# HG-Badge6.net
KiCad netlist of a schematic drawn in EAGLE
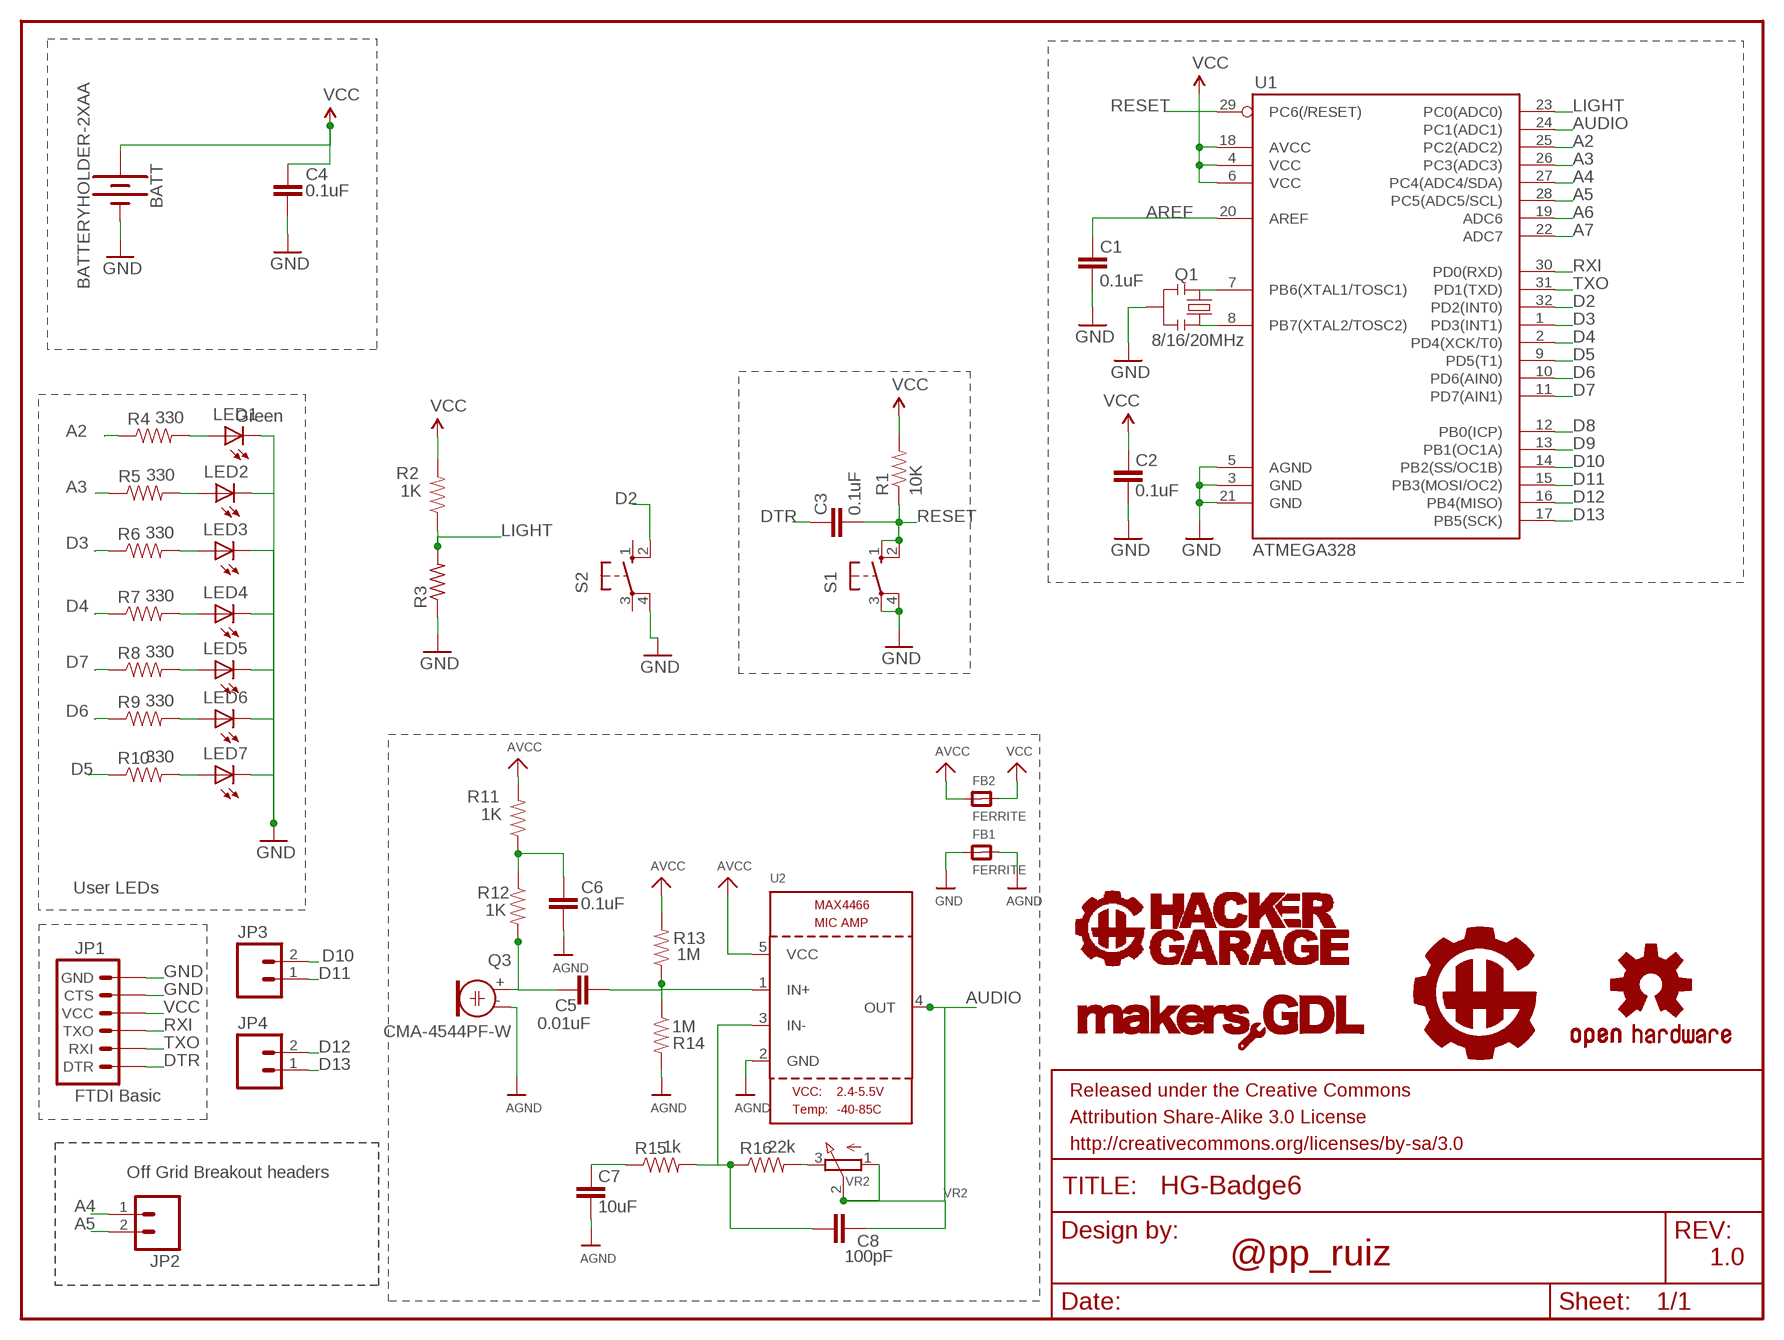
[diagram p0: schematic, sheet 1]

(export (version "E")
  (design (tool "Eeschema 10.0.6"))
  (components
    (comp (ref "BATT")
      (value "BATTERYHOLDER-2XAA")
      (footprint "eagle-import:BATT-HOLDER-2XAAA")
      (libsource (lib "eagle-import") (part "BATTERYHOLDER-2XAA"))
    )
    (comp (ref "C1")
      (value "0.1uF")
      (footprint "eagle-import:0603-CAP")
      (libsource (lib "eagle-import") (part "CAP0603-CAP"))
    )
    (comp (ref "C2")
      (value "0.1uF")
      (footprint "eagle-import:0603-CAP")
      (libsource (lib "eagle-import") (part "CAP0603-CAP"))
    )
    (comp (ref "C3")
      (value "0.1uF")
      (footprint "eagle-import:0603-CAP")
      (libsource (lib "eagle-import") (part "CAP0603-CAP"))
    )
    (comp (ref "C4")
      (value "0.1uF")
      (footprint "eagle-import:0603-CAP")
      (libsource (lib "eagle-import") (part "CAP0603-CAP"))
    )
    (comp (ref "C5")
      (value "0.01uF")
      (footprint "eagle-import:0603-CAP")
      (libsource (lib "eagle-import") (part "CAP0603-CAP"))
    )
    (comp (ref "C6")
      (value "0.1uF")
      (footprint "eagle-import:0603-CAP")
      (libsource (lib "eagle-import") (part "CAP0603-CAP"))
    )
    (comp (ref "C7")
      (value "10uF")
      (footprint "eagle-import:0603-CAP")
      (libsource (lib "eagle-import") (part "CAP0603-CAP"))
    )
    (comp (ref "C8")
      (value "100pF")
      (footprint "eagle-import:0603-CAP")
      (libsource (lib "eagle-import") (part "CAP0603-CAP"))
    )
    (comp (ref "FB1")
      (value "FERRITE")
      (footprint "eagle-import:0805")
      (libsource (lib "eagle-import") (part "FERRITE0805"))
    )
    (comp (ref "FB2")
      (value "FERRITE")
      (footprint "eagle-import:0805")
      (libsource (lib "eagle-import") (part "FERRITE0805"))
    )
    (comp (ref "FRAME1")
      (value "FRAME-LETTER")
      (footprint "eagle-import:CREATIVE_COMMONS")
      (libsource (lib "eagle-import") (part "FRAME-LETTER"))
    )
    (comp (ref "JP1")
      (value "FTDI Basic")
      (footprint "eagle-import:1X06")
      (libsource (lib "eagle-import") (part "ARDUINO_SERIAL_PROGRAMPTH"))
    )
    (comp (ref "JP2")
      (value "M02PTH")
      (footprint "eagle-import:1X02")
      (libsource (lib "eagle-import") (part "M02PTH"))
    )
    (comp (ref "JP3")
      (value "M02PTH")
      (footprint "eagle-import:1X02")
      (libsource (lib "eagle-import") (part "M02PTH"))
    )
    (comp (ref "JP4")
      (value "M02PTH")
      (footprint "eagle-import:1X02")
      (libsource (lib "eagle-import") (part "M02PTH"))
    )
    (comp (ref "LED1")
      (value "Green")
      (footprint "eagle-import:0603-LED-ALT1")
      (libsource (lib "eagle-import") (part "LED"))
    )
    (comp (ref "LED2")
      (value "Green")
      (footprint "eagle-import:0603-LED-ALT1")
      (libsource (lib "eagle-import") (part "LED"))
    )
    (comp (ref "LED3")
      (value "Green")
      (footprint "eagle-import:0603-LED-ALT1")
      (libsource (lib "eagle-import") (part "LED"))
    )
    (comp (ref "LED4")
      (value "Green")
      (footprint "eagle-import:0603-LED-ALT1")
      (libsource (lib "eagle-import") (part "LED"))
    )
    (comp (ref "LED5")
      (value "Green")
      (footprint "eagle-import:0603-LED-ALT1")
      (libsource (lib "eagle-import") (part "LED"))
    )
    (comp (ref "LED6")
      (value "Green")
      (footprint "eagle-import:0603-LED-ALT1")
      (libsource (lib "eagle-import") (part "LED"))
    )
    (comp (ref "LED7")
      (value "Green")
      (footprint "eagle-import:0603-LED-ALT1")
      (libsource (lib "eagle-import") (part "LED"))
    )
    (comp (ref "Q1")
      (value "8/16/20MHz")
      (footprint "eagle-import:RESONATOR-SMD-1_1")
      (libsource (lib "eagle-import") (part "RESONATOR1{colon}1"))
    )
    (comp (ref "Q3")
      (value "CMA-4544PF-W")
      (footprint "eagle-import:ELECTRET_9.7")
      (libsource (lib "eagle-import") (part "ELECTRET"))
    )
    (comp (ref "R1")
      (value "10K")
      (footprint "eagle-import:0603-RES")
      (libsource (lib "eagle-import") (part "RESISTOR0603-RES"))
    )
    (comp (ref "R2")
      (value "1K")
      (footprint "eagle-import:0603-RES")
      (libsource (lib "eagle-import") (part "RESISTOR0603-RES"))
    )
    (comp (ref "R3")
      (value "R-US_0204/2V")
      (footprint "eagle-import:0204V")
      (libsource (lib "eagle-import") (part "R-US_0204/2V"))
    )
    (comp (ref "R4")
      (value "330")
      (footprint "eagle-import:0603-RES")
      (libsource (lib "eagle-import") (part "RESISTOR0603-RES"))
    )
    (comp (ref "R5")
      (value "330")
      (footprint "eagle-import:0603-RES")
      (libsource (lib "eagle-import") (part "RESISTOR0603-RES"))
    )
    (comp (ref "R6")
      (value "330")
      (footprint "eagle-import:0603-RES")
      (libsource (lib "eagle-import") (part "RESISTOR0603-RES"))
    )
    (comp (ref "R7")
      (value "330")
      (footprint "eagle-import:0603-RES")
      (libsource (lib "eagle-import") (part "RESISTOR0603-RES"))
    )
    (comp (ref "R8")
      (value "330")
      (footprint "eagle-import:0603-RES")
      (libsource (lib "eagle-import") (part "RESISTOR0603-RES"))
    )
    (comp (ref "R9")
      (value "330")
      (footprint "eagle-import:0603-RES")
      (libsource (lib "eagle-import") (part "RESISTOR0603-RES"))
    )
    (comp (ref "R10")
      (value "330")
      (footprint "eagle-import:0603-RES")
      (libsource (lib "eagle-import") (part "RESISTOR0603-RES"))
    )
    (comp (ref "R11")
      (value "1K")
      (footprint "eagle-import:0603-RES")
      (libsource (lib "eagle-import") (part "RESISTOR0603-RES"))
    )
    (comp (ref "R12")
      (value "1K")
      (footprint "eagle-import:0603-RES")
      (libsource (lib "eagle-import") (part "RESISTOR0603-RES"))
    )
    (comp (ref "R13")
      (value "1M")
      (footprint "eagle-import:0603-RES")
      (libsource (lib "eagle-import") (part "RESISTOR0603-RES"))
    )
    (comp (ref "R14")
      (value "1M")
      (footprint "eagle-import:0603-RES")
      (libsource (lib "eagle-import") (part "RESISTOR0603-RES"))
    )
    (comp (ref "R15")
      (value "1k")
      (footprint "eagle-import:0603-RES")
      (libsource (lib "eagle-import") (part "RESISTOR0603-RES"))
    )
    (comp (ref "R16")
      (value "22k")
      (footprint "eagle-import:0603-RES")
      (libsource (lib "eagle-import") (part "RESISTOR0603-RES"))
    )
    (comp (ref "S1")
      (value "10-XX")
      (footprint "eagle-import:B3F-10XX")
      (fields (field (name "MPN") "B3F-1000"))
      (libsource (lib "eagle-import") (part "10-XX"))
    )
    (comp (ref "S2")
      (value "10-XX")
      (footprint "eagle-import:B3F-10XX")
      (fields (field (name "MPN") "B3F-1000"))
      (libsource (lib "eagle-import") (part "10-XX"))
    )
    (comp (ref "U$1")
      (value "HG-BADGE-FULL")
      (footprint "eagle-import:HG-BADGE")
      (libsource (lib "eagle-import") (part "HG-BADGE-FULL"))
    )
    (comp (ref "U$3")
      (value "OSHW-LOGOS")
      (footprint "eagle-import:OSHW-LOGO-S")
      (libsource (lib "eagle-import") (part "OSHW-LOGOS"))
    )
    (comp (ref "U$4")
      (value "MAKERSGDLLOGO-SMALL")
      (footprint "eagle-import:MAKERSGGL-SMALL")
      (libsource (lib "eagle-import") (part "MAKERSGDLLOGO-SMALL"))
    )
    (comp (ref "U$5")
      (value "HACKERGARAGEFULL")
      (footprint "eagle-import:HACKERGARAGEFULL-SMALL")
      (libsource (lib "eagle-import") (part "HACKERGARAGEFULL"))
    )
    (comp (ref "U1")
      (value "ATMEGA328")
      (footprint "eagle-import:TQFP32-08")
      (libsource (lib "eagle-import") (part "ATMEGA168"))
    )
    (comp (ref "U2")
      (value "MAX4466EXK+T")
      (footprint "eagle-import:SC70-5")
      (libsource (lib "eagle-import") (part "MAX4466{dblquote}{dblquote}"))
    )
    (comp (ref "VR2")
      (value "VR2")
      (footprint "eagle-import:TRIMPOT_BOURNS_TC33X-2")
      (libsource (lib "eagle-import") (part "TRIMPOTTC33X-2"))
    )
  )
  (nets
    (net (code "1") (name "/A2") (class "Default")
      (node (ref "R4") (pin "1") (pinfunction "1_1") (pintype "passive"))
      (node (ref "U1") (pin "25") (pinfunction "PC2(ADC2)_25") (pintype "bidirectional"))
    )
    (net (code "2") (name "/A3") (class "Default")
      (node (ref "R5") (pin "1") (pinfunction "1_1") (pintype "passive"))
      (node (ref "U1") (pin "26") (pinfunction "PC3(ADC3)_26") (pintype "bidirectional"))
    )
    (net (code "3") (name "/A4") (class "Default")
      (node (ref "JP2") (pin "1") (pinfunction "1_1") (pintype "passive"))
      (node (ref "U1") (pin "27") (pinfunction "PC4(ADC4/SDA)_27") (pintype "bidirectional"))
    )
    (net (code "4") (name "/A5") (class "Default")
      (node (ref "JP2") (pin "2") (pinfunction "2_2") (pintype "passive"))
      (node (ref "U1") (pin "28") (pinfunction "PC5(ADC5/SCL)_28") (pintype "bidirectional"))
    )
    (net (code "5") (name "/A6") (class "Default")
      (node (ref "U1") (pin "19") (pinfunction "ADC6_19") (pintype "bidirectional"))
    )
    (net (code "6") (name "/A7") (class "Default")
      (node (ref "U1") (pin "22") (pinfunction "ADC7_22") (pintype "bidirectional"))
    )
    (net (code "7") (name "/AREF") (class "Default")
      (node (ref "C1") (pin "2") (pinfunction "2_2") (pintype "passive"))
      (node (ref "U1") (pin "20") (pinfunction "AREF_20") (pintype "bidirectional"))
    )
    (net (code "8") (name "/AUDIO") (class "Default")
      (node (ref "C8") (pin "1") (pinfunction "1_1") (pintype "passive"))
      (node (ref "U1") (pin "24") (pinfunction "PC1(ADC1)_24") (pintype "bidirectional"))
      (node (ref "U2") (pin "4") (pinfunction "OUT_4") (pintype "bidirectional"))
      (node (ref "VR2") (pin "1") (pinfunction "A_1") (pintype "passive"))
      (node (ref "VR2") (pin "2") (pinfunction "S_2") (pintype "passive"))
    )
    (net (code "9") (name "/D2") (class "Default")
      (node (ref "S2") (pin "2") (pinfunction "S1_2") (pintype "passive"))
      (node (ref "U1") (pin "32") (pinfunction "PD2(INT0)_32") (pintype "bidirectional"))
    )
    (net (code "10") (name "/D3") (class "Default")
      (node (ref "R6") (pin "1") (pinfunction "1_1") (pintype "passive"))
      (node (ref "U1") (pin "1") (pinfunction "PD3(INT1)_1") (pintype "bidirectional"))
    )
    (net (code "11") (name "/D4") (class "Default")
      (node (ref "R7") (pin "1") (pinfunction "1_1") (pintype "passive"))
      (node (ref "U1") (pin "2") (pinfunction "PD4(XCK/T0)_2") (pintype "bidirectional"))
    )
    (net (code "12") (name "/D5") (class "Default")
      (node (ref "R10") (pin "1") (pinfunction "1_1") (pintype "passive"))
      (node (ref "U1") (pin "9") (pinfunction "PD5(T1)_9") (pintype "bidirectional"))
    )
    (net (code "13") (name "/D6") (class "Default")
      (node (ref "R9") (pin "1") (pinfunction "1_1") (pintype "passive"))
      (node (ref "U1") (pin "10") (pinfunction "PD6(AIN0)_10") (pintype "bidirectional"))
    )
    (net (code "14") (name "/D7") (class "Default")
      (node (ref "R8") (pin "1") (pinfunction "1_1") (pintype "passive"))
      (node (ref "U1") (pin "11") (pinfunction "PD7(AIN1)_11") (pintype "bidirectional"))
    )
    (net (code "15") (name "/D8") (class "Default")
      (node (ref "U1") (pin "12") (pinfunction "PB0(ICP)_12") (pintype "bidirectional"))
    )
    (net (code "16") (name "/D9") (class "Default")
      (node (ref "U1") (pin "13") (pinfunction "PB1(OC1A)_13") (pintype "bidirectional"))
    )
    (net (code "17") (name "/D10") (class "Default")
      (node (ref "JP3") (pin "2") (pinfunction "2_2") (pintype "passive"))
      (node (ref "U1") (pin "14") (pinfunction "PB2(SS/OC1B)_14") (pintype "bidirectional"))
    )
    (net (code "18") (name "/D11") (class "Default")
      (node (ref "JP3") (pin "1") (pinfunction "1_1") (pintype "passive"))
      (node (ref "U1") (pin "15") (pinfunction "PB3(MOSI/OC2)_15") (pintype "bidirectional"))
    )
    (net (code "19") (name "/D12") (class "Default")
      (node (ref "JP4") (pin "2") (pinfunction "2_2") (pintype "passive"))
      (node (ref "U1") (pin "16") (pinfunction "PB4(MISO)_16") (pintype "bidirectional"))
    )
    (net (code "20") (name "/D13") (class "Default")
      (node (ref "JP4") (pin "1") (pinfunction "1_1") (pintype "passive"))
      (node (ref "U1") (pin "17") (pinfunction "PB5(SCK)_17") (pintype "bidirectional"))
    )
    (net (code "21") (name "/DTR") (class "Default")
      (node (ref "C3") (pin "2") (pinfunction "2_2") (pintype "passive"))
      (node (ref "JP1") (pin "1") (pinfunction "DTR_1") (pintype "passive"))
    )
    (net (code "22") (name "/LIGHT") (class "Default")
      (node (ref "R2") (pin "1") (pinfunction "1_1") (pintype "passive"))
      (node (ref "R3") (pin "2") (pinfunction "2_2") (pintype "passive"))
      (node (ref "U1") (pin "23") (pinfunction "PC0(ADC0)_23") (pintype "bidirectional"))
    )
    (net (code "23") (name "/RESET") (class "Default")
      (node (ref "C3") (pin "1") (pinfunction "1_1") (pintype "passive"))
      (node (ref "R1") (pin "1") (pinfunction "1_1") (pintype "passive"))
      (node (ref "S1") (pin "1") (pinfunction "S_1") (pintype "passive"))
      (node (ref "S1") (pin "2") (pinfunction "S1_2") (pintype "passive"))
      (node (ref "U1") (pin "29") (pinfunction "PC6(/RESET)_29") (pintype "bidirectional"))
    )
    (net (code "24") (name "/RXI") (class "Default")
      (node (ref "JP1") (pin "3") (pinfunction "TXO_3") (pintype "passive"))
      (node (ref "U1") (pin "30") (pinfunction "PD0(RXD)_30") (pintype "bidirectional"))
    )
    (net (code "25") (name "/TXO") (class "Default")
      (node (ref "JP1") (pin "2") (pinfunction "RXI_2") (pintype "passive"))
      (node (ref "U1") (pin "31") (pinfunction "PD1(TXD)_31") (pintype "bidirectional"))
    )
    (net (code "26") (name "AGND") (class "Default")
      (node (ref "C6") (pin "1") (pinfunction "1_1") (pintype "passive"))
      (node (ref "C7") (pin "1") (pinfunction "1_1") (pintype "passive"))
      (node (ref "FB1") (pin "2") (pinfunction "P$2_2") (pintype "passive"))
      (node (ref "Q3") (pin "-") (pinfunction "1_-") (pintype "passive"))
      (node (ref "R14") (pin "2") (pinfunction "2_2") (pintype "passive"))
      (node (ref "U2") (pin "2") (pinfunction "GND_2") (pintype "bidirectional"))
    )
    (net (code "27") (name "AVCC") (class "Default")
      (node (ref "FB2") (pin "1") (pinfunction "P$1_1") (pintype "passive"))
      (node (ref "R11") (pin "2") (pinfunction "2_2") (pintype "passive"))
      (node (ref "R13") (pin "2") (pinfunction "2_2") (pintype "passive"))
      (node (ref "U2") (pin "5") (pinfunction "VCC_5") (pintype "bidirectional"))
    )
    (net (code "28") (name "GND") (class "Default")
      (node (ref "BATT") (pin "P$1") (pinfunction "-_P$1") (pintype "power_in"))
      (node (ref "C1") (pin "1") (pinfunction "1_1") (pintype "passive"))
      (node (ref "C2") (pin "1") (pinfunction "1_1") (pintype "passive"))
      (node (ref "C4") (pin "1") (pinfunction "1_1") (pintype "passive"))
      (node (ref "FB1") (pin "1") (pinfunction "P$1_1") (pintype "passive"))
      (node (ref "JP1") (pin "5") (pinfunction "CTS_5") (pintype "passive"))
      (node (ref "JP1") (pin "6") (pinfunction "GND_6") (pintype "passive"))
      (node (ref "LED1") (pin "C") (pinfunction "C_C") (pintype "passive"))
      (node (ref "LED2") (pin "C") (pinfunction "C_C") (pintype "passive"))
      (node (ref "LED3") (pin "C") (pinfunction "C_C") (pintype "passive"))
      (node (ref "LED4") (pin "C") (pinfunction "C_C") (pintype "passive"))
      (node (ref "LED5") (pin "C") (pinfunction "C_C") (pintype "passive"))
      (node (ref "LED6") (pin "C") (pinfunction "C_C") (pintype "passive"))
      (node (ref "LED7") (pin "C") (pinfunction "C_C") (pintype "passive"))
      (node (ref "Q1") (pin "2") (pinfunction "2_2") (pintype "passive"))
      (node (ref "R3") (pin "1") (pinfunction "1_1") (pintype "passive"))
      (node (ref "S1") (pin "3") (pinfunction "P_3") (pintype "passive"))
      (node (ref "S1") (pin "4") (pinfunction "P1_4") (pintype "passive"))
      (node (ref "S2") (pin "4") (pinfunction "P1_4") (pintype "passive"))
      (node (ref "U1") (pin "21") (pinfunction "GND_21") (pintype "bidirectional"))
      (node (ref "U1") (pin "3") (pinfunction "GND_3") (pintype "bidirectional"))
      (node (ref "U1") (pin "5") (pinfunction "AGND_5") (pintype "bidirectional"))
    )
    (net (code "29") (name "Net-(C6-Pad2)") (class "Default")
      (node (ref "C6") (pin "2") (pinfunction "2_2") (pintype "passive"))
      (node (ref "R11") (pin "1") (pinfunction "1_1") (pintype "passive"))
      (node (ref "R12") (pin "1") (pinfunction "1_1") (pintype "passive"))
    )
    (net (code "30") (name "Net-(C7-Pad2)") (class "Default")
      (node (ref "C7") (pin "2") (pinfunction "2_2") (pintype "passive"))
      (node (ref "R15") (pin "1") (pinfunction "1_1") (pintype "passive"))
    )
    (net (code "31") (name "Net-(LED1-PadA)") (class "Default")
      (node (ref "LED1") (pin "A") (pinfunction "A_A") (pintype "passive"))
      (node (ref "R4") (pin "2") (pinfunction "2_2") (pintype "passive"))
    )
    (net (code "32") (name "Net-(LED2-PadA)") (class "Default")
      (node (ref "LED2") (pin "A") (pinfunction "A_A") (pintype "passive"))
      (node (ref "R5") (pin "2") (pinfunction "2_2") (pintype "passive"))
    )
    (net (code "33") (name "Net-(LED3-PadA)") (class "Default")
      (node (ref "LED3") (pin "A") (pinfunction "A_A") (pintype "passive"))
      (node (ref "R6") (pin "2") (pinfunction "2_2") (pintype "passive"))
    )
    (net (code "34") (name "Net-(LED4-PadA)") (class "Default")
      (node (ref "LED4") (pin "A") (pinfunction "A_A") (pintype "passive"))
      (node (ref "R7") (pin "2") (pinfunction "2_2") (pintype "passive"))
    )
    (net (code "35") (name "Net-(LED5-PadA)") (class "Default")
      (node (ref "LED5") (pin "A") (pinfunction "A_A") (pintype "passive"))
      (node (ref "R8") (pin "2") (pinfunction "2_2") (pintype "passive"))
    )
    (net (code "36") (name "Net-(LED6-PadA)") (class "Default")
      (node (ref "LED6") (pin "A") (pinfunction "A_A") (pintype "passive"))
      (node (ref "R9") (pin "2") (pinfunction "2_2") (pintype "passive"))
    )
    (net (code "37") (name "Net-(LED7-PadA)") (class "Default")
      (node (ref "LED7") (pin "A") (pinfunction "A_A") (pintype "passive"))
      (node (ref "R10") (pin "2") (pinfunction "2_2") (pintype "passive"))
    )
    (net (code "38") (name "Net-(Q3-2)") (class "Default")
      (node (ref "C5") (pin "2") (pinfunction "2_2") (pintype "passive"))
      (node (ref "Q3") (pin "+") (pinfunction "2_+") (pintype "passive"))
      (node (ref "R12") (pin "2") (pinfunction "2_2") (pintype "passive"))
    )
    (net (code "39") (name "Net-(U1-PB6(XTAL1{slash}TOSC1))") (class "Default")
      (node (ref "Q1") (pin "1") (pinfunction "1_1") (pintype "passive"))
      (node (ref "U1") (pin "7") (pinfunction "PB6(XTAL1/TOSC1)_7") (pintype "bidirectional"))
    )
    (net (code "40") (name "Net-(U1-PB7(XTAL2{slash}TOSC2))") (class "Default")
      (node (ref "Q1") (pin "3") (pinfunction "3_3") (pintype "passive"))
      (node (ref "U1") (pin "8") (pinfunction "PB7(XTAL2/TOSC2)_8") (pintype "bidirectional"))
    )
    (net (code "41") (name "Net-(U2-IN+)") (class "Default")
      (node (ref "C5") (pin "1") (pinfunction "1_1") (pintype "passive"))
      (node (ref "R13") (pin "1") (pinfunction "1_1") (pintype "passive"))
      (node (ref "R14") (pin "1") (pinfunction "1_1") (pintype "passive"))
      (node (ref "U2") (pin "1") (pinfunction "IN+_1") (pintype "bidirectional"))
    )
    (net (code "42") (name "Net-(U2-IN-)") (class "Default")
      (node (ref "C8") (pin "2") (pinfunction "2_2") (pintype "passive"))
      (node (ref "R15") (pin "2") (pinfunction "2_2") (pintype "passive"))
      (node (ref "R16") (pin "1") (pinfunction "1_1") (pintype "passive"))
      (node (ref "U2") (pin "3") (pinfunction "IN-_3") (pintype "bidirectional"))
    )
    (net (code "43") (name "Net-(VR2-E)") (class "Default")
      (node (ref "R16") (pin "2") (pinfunction "2_2") (pintype "passive"))
      (node (ref "VR2") (pin "3") (pinfunction "E_3") (pintype "passive"))
    )
    (net (code "44") (name "VCC") (class "Default")
      (node (ref "BATT") (pin "P$2") (pinfunction "+_P$2") (pintype "power_in"))
      (node (ref "C2") (pin "2") (pinfunction "2_2") (pintype "passive"))
      (node (ref "C4") (pin "2") (pinfunction "2_2") (pintype "passive"))
      (node (ref "FB2") (pin "2") (pinfunction "P$2_2") (pintype "passive"))
      (node (ref "JP1") (pin "4") (pinfunction "VCC_4") (pintype "passive"))
      (node (ref "R1") (pin "2") (pinfunction "2_2") (pintype "passive"))
      (node (ref "R2") (pin "2") (pinfunction "2_2") (pintype "passive"))
      (node (ref "U1") (pin "18") (pinfunction "AVCC_18") (pintype "bidirectional"))
      (node (ref "U1") (pin "4") (pinfunction "VCC_4") (pintype "bidirectional"))
      (node (ref "U1") (pin "6") (pinfunction "VCC_6") (pintype "bidirectional"))
    )
    (net (code "45") (name "unconnected-(S2-P-Pad3)") (class "Default")
      (node (ref "S2") (pin "3") (pinfunction "P_3") (pintype "passive"))
    )
    (net (code "46") (name "unconnected-(S2-S-Pad1)") (class "Default")
      (node (ref "S2") (pin "1") (pinfunction "S_1") (pintype "passive"))
    )
  )
)
